# Adafruit_6-ISP_AVR.net
KiCad netlist of a schematic drawn in EAGLE
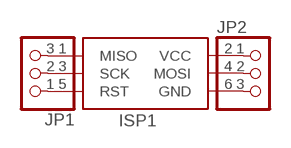
[diagram p0: schematic, sheet 1]

(export (version "E")
  (design (tool "Eeschema 10.0.6"))
  (components
    (comp (ref "ISP1")
      (value "AVRISP-BOX")
      (footprint "eagle-import:AVRISP-BOX")
      (libsource (lib "eagle-import") (part "AVRISP-BOX"))
    )
    (comp (ref "JP1")
      (value "PINHD-1X3CB")
      (footprint "eagle-import:1X03-CLEANBIG")
      (libsource (lib "eagle-import") (part "PINHD-1X3CB"))
    )
    (comp (ref "JP2")
      (value "PINHD-1X3CB")
      (footprint "eagle-import:1X03-CLEANBIG")
      (libsource (lib "eagle-import") (part "PINHD-1X3CB"))
    )
  )
  (nets
    (net (code "1") (name "Net-(ISP1-GND)") (class "Default")
      (node (ref "ISP1") (pin "6") (pinfunction "GND_6") (pintype "power_in"))
      (node (ref "JP2") (pin "3") (pinfunction "3_3") (pintype "passive"))
    )
    (net (code "2") (name "Net-(ISP1-MISO)") (class "Default")
      (node (ref "ISP1") (pin "1") (pinfunction "MISO_1") (pintype "input"))
      (node (ref "JP1") (pin "3") (pinfunction "3_3") (pintype "passive"))
    )
    (net (code "3") (name "Net-(ISP1-MOSI)") (class "Default")
      (node (ref "ISP1") (pin "4") (pinfunction "MOSI_4") (pintype "output"))
      (node (ref "JP2") (pin "2") (pinfunction "2_2") (pintype "passive"))
    )
    (net (code "4") (name "Net-(ISP1-RST)") (class "Default")
      (node (ref "ISP1") (pin "5") (pinfunction "RST_5") (pintype "output"))
      (node (ref "JP1") (pin "1") (pinfunction "1_1") (pintype "passive"))
    )
    (net (code "5") (name "Net-(ISP1-SCK)") (class "Default")
      (node (ref "ISP1") (pin "3") (pinfunction "SCK_3") (pintype "output"))
      (node (ref "JP1") (pin "2") (pinfunction "2_2") (pintype "passive"))
    )
    (net (code "6") (name "Net-(ISP1-VCC)") (class "Default")
      (node (ref "ISP1") (pin "2") (pinfunction "VCC_2") (pintype "power_in"))
      (node (ref "JP2") (pin "1") (pinfunction "1_1") (pintype "passive"))
    )
  )
)
